# Power_module_Mini.net
KiCad netlist of a schematic drawn in EAGLE
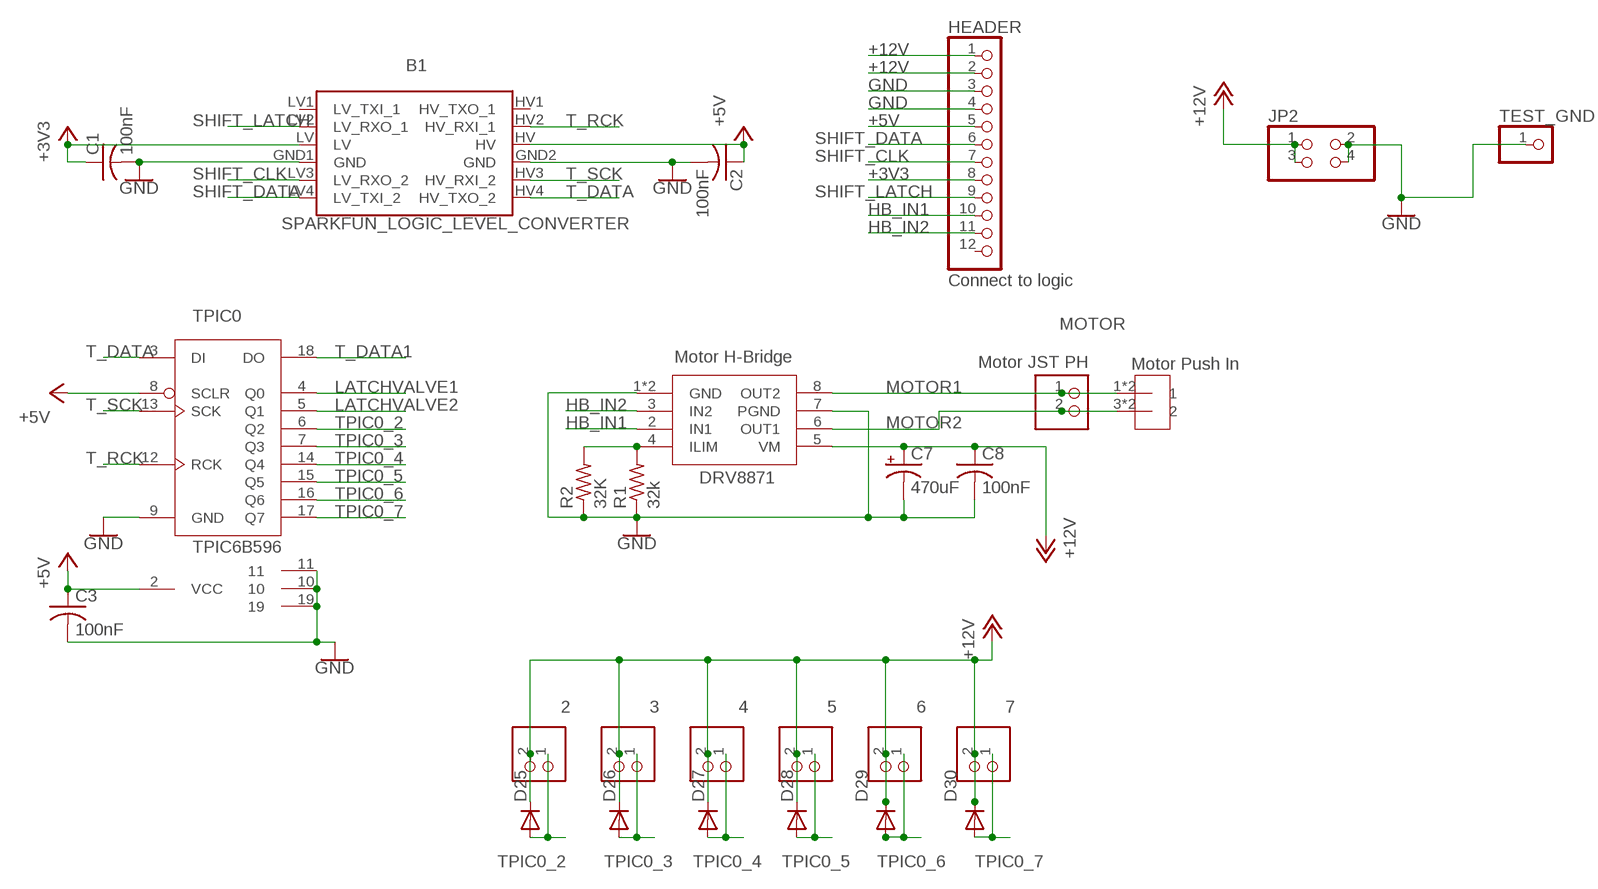
[diagram p0: schematic, sheet 1]

(export (version "E")
  (design (tool "Eeschema 10.0.6"))
  (components
    (comp (ref "2")
      (value "2.5MM_JST_UP_2POS")
      (footprint "eagle-import:JST_2POS_2.5MM_UP")
      (libsource (lib "eagle-import") (part "2.5MM_JST_UP_2POS"))
    )
    (comp (ref "3")
      (value "2.5MM_JST_UP_2POS")
      (footprint "eagle-import:JST_2POS_2.5MM_UP")
      (libsource (lib "eagle-import") (part "2.5MM_JST_UP_2POS"))
    )
    (comp (ref "4")
      (value "2.5MM_JST_UP_2POS")
      (footprint "eagle-import:JST_2POS_2.5MM_UP")
      (libsource (lib "eagle-import") (part "2.5MM_JST_UP_2POS"))
    )
    (comp (ref "5")
      (value "2.5MM_JST_UP_2POS")
      (footprint "eagle-import:JST_2POS_2.5MM_UP")
      (libsource (lib "eagle-import") (part "2.5MM_JST_UP_2POS"))
    )
    (comp (ref "6")
      (value "2.5MM_JST_UP_2POS")
      (footprint "eagle-import:JST_2POS_2.5MM_UP")
      (libsource (lib "eagle-import") (part "2.5MM_JST_UP_2POS"))
    )
    (comp (ref "7")
      (value "2.5MM_JST_UP_2POS")
      (footprint "eagle-import:JST_2POS_2.5MM_UP")
      (libsource (lib "eagle-import") (part "2.5MM_JST_UP_2POS"))
    )
    (comp (ref "B1")
      (value "SPARKFUN_LOGIC_LEVEL_CONVERTER")
      (footprint "eagle-import:SPARKFUN_LOGIC_LEVEL_CONVERTER")
      (libsource (lib "eagle-import") (part "SPARKFUN_LOGIC_LEVEL_CONVERTER"))
    )
    (comp (ref "C1")
      (value "100nF")
      (footprint "eagle-import:C1206")
      (libsource (lib "eagle-import") (part "C-USC1206"))
    )
    (comp (ref "C2")
      (value "100nF")
      (footprint "eagle-import:C1206")
      (libsource (lib "eagle-import") (part "C-USC1206"))
    )
    (comp (ref "C3")
      (value "100nF")
      (footprint "eagle-import:C1206")
      (libsource (lib "eagle-import") (part "C-USC1206"))
    )
    (comp (ref "C7")
      (value "470uF")
      (footprint "eagle-import:140CLH-0810")
      (libsource (lib "eagle-import") (part "CPOL-US140CLH-0810"))
    )
    (comp (ref "C8")
      (value "100nF")
      (footprint "eagle-import:C1206")
      (libsource (lib "eagle-import") (part "C-USC1206"))
    )
    (comp (ref "D25")
      (value "DIODESOD-123")
      (footprint "eagle-import:SOD-123")
      (libsource (lib "eagle-import") (part "DIODESOD-123"))
    )
    (comp (ref "D26")
      (value "DIODESOD-123")
      (footprint "eagle-import:SOD-123")
      (libsource (lib "eagle-import") (part "DIODESOD-123"))
    )
    (comp (ref "D27")
      (value "DIODESOD-123")
      (footprint "eagle-import:SOD-123")
      (libsource (lib "eagle-import") (part "DIODESOD-123"))
    )
    (comp (ref "D28")
      (value "DIODESOD-123")
      (footprint "eagle-import:SOD-123")
      (libsource (lib "eagle-import") (part "DIODESOD-123"))
    )
    (comp (ref "D29")
      (value "DIODESOD-123")
      (footprint "eagle-import:SOD-123")
      (libsource (lib "eagle-import") (part "DIODESOD-123"))
    )
    (comp (ref "D30")
      (value "DIODESOD-123")
      (footprint "eagle-import:SOD-123")
      (libsource (lib "eagle-import") (part "DIODESOD-123"))
    )
    (comp (ref "DRV8871")
      (value "Motor H-Bridge")
      (footprint "eagle-import:SOP8")
      (libsource (lib "eagle-import") (part "DRV8871"))
    )
    (comp (ref "HEADER")
      (value "Connect to logic")
      (footprint "eagle-import:1X12")
      (libsource (lib "eagle-import") (part "PINHD-1X12"))
    )
    (comp (ref "JP2")
      (value "PINHD-2X2")
      (footprint "eagle-import:2X02")
      (libsource (lib "eagle-import") (part "PINHD-2X2"))
    )
    (comp (ref "MOTOR")
      (value "Motor JST PH")
      (footprint "eagle-import:JST_2POS_2.5MM_UP")
      (libsource (lib "eagle-import") (part "2.5MM_JST_UP_2POS"))
    )
    (comp (ref "R1")
      (value "32k")
      (footprint "eagle-import:0204_5")
      (libsource (lib "eagle-import") (part "R-US_0204/5"))
    )
    (comp (ref "R2")
      (value "32K")
      (footprint "eagle-import:R0805")
      (libsource (lib "eagle-import") (part "rcl_334_R-US_R0805"))
    )
    (comp (ref "TEST_GND")
      (value "PINHD-1X1")
      (footprint "eagle-import:1X01")
      (libsource (lib "eagle-import") (part "PINHD-1X1"))
    )
    (comp (ref "TPIC0")
      (value "TPIC6B596")
      (footprint "eagle-import:DIP20")
      (libsource (lib "eagle-import") (part "TPIC6B596"))
    )
    (comp (ref "U$1")
      (value "Motor Push In")
      (footprint "eagle-import:3.5MM_DIP2")
      (libsource (lib "eagle-import") (part "PUSH_IN_2"))
    )
  )
  (nets
    (net (code "1") (name "+3V3") (class "Default")
      (node (ref "B1") (pin "LV") (pinfunction "LV_LV") (pintype "power_in"))
      (node (ref "C1") (pin "1") (pinfunction "1_1") (pintype "passive"))
      (node (ref "HEADER") (pin "8") (pinfunction "8_8") (pintype "passive"))
    )
    (net (code "2") (name "+5V") (class "Default")
      (node (ref "B1") (pin "HV") (pinfunction "HV_HV") (pintype "power_in"))
      (node (ref "C2") (pin "1") (pinfunction "1_1") (pintype "passive"))
      (node (ref "C3") (pin "1") (pinfunction "1_1") (pintype "passive"))
      (node (ref "HEADER") (pin "5") (pinfunction "5_5") (pintype "passive"))
      (node (ref "TPIC0") (pin "2") (pinfunction "VCC_2") (pintype "bidirectional"))
      (node (ref "TPIC0") (pin "8") (pinfunction "SCLR_8") (pintype "bidirectional"))
    )
    (net (code "3") (name "+12V") (class "Default")
      (node (ref "2") (pin "2") (pinfunction "2_2") (pintype "bidirectional"))
      (node (ref "3") (pin "2") (pinfunction "2_2") (pintype "bidirectional"))
      (node (ref "4") (pin "2") (pinfunction "2_2") (pintype "bidirectional"))
      (node (ref "5") (pin "2") (pinfunction "2_2") (pintype "bidirectional"))
      (node (ref "6") (pin "2") (pinfunction "2_2") (pintype "bidirectional"))
      (node (ref "7") (pin "2") (pinfunction "2_2") (pintype "bidirectional"))
      (node (ref "C7") (pin "+") (pinfunction "+_+") (pintype "passive"))
      (node (ref "C8") (pin "1") (pinfunction "1_1") (pintype "passive"))
      (node (ref "D25") (pin "C") (pinfunction "C_C") (pintype "passive"))
      (node (ref "D26") (pin "C") (pinfunction "C_C") (pintype "passive"))
      (node (ref "D27") (pin "C") (pinfunction "C_C") (pintype "passive"))
      (node (ref "D28") (pin "C") (pinfunction "C_C") (pintype "passive"))
      (node (ref "D29") (pin "C") (pinfunction "C_C") (pintype "passive"))
      (node (ref "D30") (pin "C") (pinfunction "C_C") (pintype "passive"))
      (node (ref "DRV8871") (pin "5") (pinfunction "VM_5") (pintype "bidirectional"))
      (node (ref "HEADER") (pin "1") (pinfunction "1_1") (pintype "passive"))
      (node (ref "HEADER") (pin "2") (pinfunction "2_2") (pintype "passive"))
      (node (ref "JP2") (pin "1") (pinfunction "1_1") (pintype "passive"))
      (node (ref "JP2") (pin "3") (pinfunction "3_3") (pintype "passive"))
    )
    (net (code "4") (name "/HB_IN1") (class "Default")
      (node (ref "DRV8871") (pin "2") (pinfunction "IN1_2") (pintype "bidirectional"))
      (node (ref "HEADER") (pin "10") (pinfunction "10_10") (pintype "passive"))
    )
    (net (code "5") (name "/HB_IN2") (class "Default")
      (node (ref "DRV8871") (pin "3") (pinfunction "IN2_3") (pintype "bidirectional"))
      (node (ref "HEADER") (pin "11") (pinfunction "11_11") (pintype "passive"))
    )
    (net (code "6") (name "/LATCHVALVE1") (class "Default")
      (node (ref "TPIC0") (pin "4") (pinfunction "Q0_4") (pintype "bidirectional"))
    )
    (net (code "7") (name "/LATCHVALVE2") (class "Default")
      (node (ref "TPIC0") (pin "5") (pinfunction "Q1_5") (pintype "bidirectional"))
    )
    (net (code "8") (name "/MOTOR1") (class "Default")
      (node (ref "DRV8871") (pin "8") (pinfunction "OUT2_8") (pintype "bidirectional"))
      (node (ref "MOTOR") (pin "1") (pinfunction "1_1") (pintype "bidirectional"))
      (node (ref "U$1") (pin "1") (pinfunction "1_1") (pintype "bidirectional"))
      (node (ref "U$1") (pin "2") (pinfunction "1_2") (pintype "bidirectional"))
    )
    (net (code "9") (name "/MOTOR2") (class "Default")
      (node (ref "DRV8871") (pin "6") (pinfunction "OUT1_6") (pintype "bidirectional"))
      (node (ref "MOTOR") (pin "2") (pinfunction "2_2") (pintype "bidirectional"))
      (node (ref "U$1") (pin "3") (pinfunction "2_3") (pintype "bidirectional"))
      (node (ref "U$1") (pin "4") (pinfunction "2_4") (pintype "bidirectional"))
    )
    (net (code "10") (name "/SHIFT_CLK") (class "Default")
      (node (ref "B1") (pin "LV3") (pinfunction "LV_RXO_2_LV3") (pintype "bidirectional"))
      (node (ref "HEADER") (pin "7") (pinfunction "7_7") (pintype "passive"))
    )
    (net (code "11") (name "/SHIFT_DATA") (class "Default")
      (node (ref "B1") (pin "LV4") (pinfunction "LV_TXI_2_LV4") (pintype "bidirectional"))
      (node (ref "HEADER") (pin "6") (pinfunction "6_6") (pintype "passive"))
    )
    (net (code "12") (name "/SHIFT_LATCH") (class "Default")
      (node (ref "B1") (pin "LV2") (pinfunction "LV_RXO_1_LV2") (pintype "bidirectional"))
      (node (ref "HEADER") (pin "9") (pinfunction "9_9") (pintype "passive"))
    )
    (net (code "13") (name "/TPIC0_2") (class "Default")
      (node (ref "2") (pin "1") (pinfunction "1_1") (pintype "bidirectional"))
      (node (ref "D25") (pin "A") (pinfunction "A_A") (pintype "passive"))
      (node (ref "TPIC0") (pin "6") (pinfunction "Q2_6") (pintype "bidirectional"))
    )
    (net (code "14") (name "/TPIC0_3") (class "Default")
      (node (ref "3") (pin "1") (pinfunction "1_1") (pintype "bidirectional"))
      (node (ref "D26") (pin "A") (pinfunction "A_A") (pintype "passive"))
      (node (ref "TPIC0") (pin "7") (pinfunction "Q3_7") (pintype "bidirectional"))
    )
    (net (code "15") (name "/TPIC0_4") (class "Default")
      (node (ref "4") (pin "1") (pinfunction "1_1") (pintype "bidirectional"))
      (node (ref "D27") (pin "A") (pinfunction "A_A") (pintype "passive"))
      (node (ref "TPIC0") (pin "14") (pinfunction "Q4_14") (pintype "bidirectional"))
    )
    (net (code "16") (name "/TPIC0_5") (class "Default")
      (node (ref "5") (pin "1") (pinfunction "1_1") (pintype "bidirectional"))
      (node (ref "D28") (pin "A") (pinfunction "A_A") (pintype "passive"))
      (node (ref "TPIC0") (pin "15") (pinfunction "Q5_15") (pintype "bidirectional"))
    )
    (net (code "17") (name "/TPIC0_6") (class "Default")
      (node (ref "6") (pin "1") (pinfunction "1_1") (pintype "bidirectional"))
      (node (ref "D29") (pin "A") (pinfunction "A_A") (pintype "passive"))
      (node (ref "TPIC0") (pin "16") (pinfunction "Q6_16") (pintype "bidirectional"))
    )
    (net (code "18") (name "/TPIC0_7") (class "Default")
      (node (ref "7") (pin "1") (pinfunction "1_1") (pintype "bidirectional"))
      (node (ref "D30") (pin "A") (pinfunction "A_A") (pintype "passive"))
      (node (ref "TPIC0") (pin "17") (pinfunction "Q7_17") (pintype "bidirectional"))
    )
    (net (code "19") (name "/T_DATA") (class "Default")
      (node (ref "B1") (pin "HV4") (pinfunction "HV_TXO_2_HV4") (pintype "bidirectional"))
      (node (ref "TPIC0") (pin "3") (pinfunction "DI_3") (pintype "bidirectional"))
    )
    (net (code "20") (name "/T_DATA1") (class "Default")
      (node (ref "TPIC0") (pin "18") (pinfunction "DO_18") (pintype "bidirectional"))
    )
    (net (code "21") (name "/T_RCK") (class "Default")
      (node (ref "B1") (pin "HV2") (pinfunction "HV_RXI_1_HV2") (pintype "bidirectional"))
      (node (ref "TPIC0") (pin "12") (pinfunction "RCK_12") (pintype "bidirectional"))
    )
    (net (code "22") (name "/T_SCK") (class "Default")
      (node (ref "B1") (pin "HV3") (pinfunction "HV_RXI_2_HV3") (pintype "bidirectional"))
      (node (ref "TPIC0") (pin "13") (pinfunction "SCK_13") (pintype "bidirectional"))
    )
    (net (code "23") (name "GND") (class "Default")
      (node (ref "B1") (pin "GND1") (pinfunction "GND_GND1") (pintype "power_in"))
      (node (ref "B1") (pin "GND2") (pinfunction "GND_GND2") (pintype "power_in"))
      (node (ref "C1") (pin "2") (pinfunction "2_2") (pintype "passive"))
      (node (ref "C2") (pin "2") (pinfunction "2_2") (pintype "passive"))
      (node (ref "C3") (pin "2") (pinfunction "2_2") (pintype "passive"))
      (node (ref "C7") (pin "-") (pinfunction "-_-") (pintype "passive"))
      (node (ref "C8") (pin "2") (pinfunction "2_2") (pintype "passive"))
      (node (ref "DRV8871") (pin "1") (pinfunction "GND_1") (pintype "bidirectional"))
      (node (ref "DRV8871") (pin "7") (pinfunction "PGND_7") (pintype "bidirectional"))
      (node (ref "DRV8871") (pin "GND") (pinfunction "GND_GND") (pintype "bidirectional"))
      (node (ref "HEADER") (pin "3") (pinfunction "3_3") (pintype "passive"))
      (node (ref "HEADER") (pin "4") (pinfunction "4_4") (pintype "passive"))
      (node (ref "JP2") (pin "2") (pinfunction "2_2") (pintype "passive"))
      (node (ref "JP2") (pin "4") (pinfunction "4_4") (pintype "passive"))
      (node (ref "R1") (pin "1") (pinfunction "1_1") (pintype "passive"))
      (node (ref "R2") (pin "1") (pinfunction "1_1") (pintype "passive"))
      (node (ref "TEST_GND") (pin "1") (pinfunction "1_1") (pintype "passive"))
      (node (ref "TPIC0") (pin "10") (pinfunction "10_10") (pintype "bidirectional"))
      (node (ref "TPIC0") (pin "11") (pinfunction "11_11") (pintype "bidirectional"))
      (node (ref "TPIC0") (pin "19") (pinfunction "19_19") (pintype "bidirectional"))
      (node (ref "TPIC0") (pin "9") (pinfunction "GND_9") (pintype "bidirectional"))
    )
    (net (code "24") (name "Net-(DRV8871-ILIM)") (class "Default")
      (node (ref "DRV8871") (pin "4") (pinfunction "ILIM_4") (pintype "bidirectional"))
      (node (ref "R1") (pin "2") (pinfunction "2_2") (pintype "passive"))
      (node (ref "R2") (pin "2") (pinfunction "2_2") (pintype "passive"))
    )
    (net (code "25") (name "unconnected-(B1-HV_TXO_1-PadHV1)") (class "Default")
      (node (ref "B1") (pin "HV1") (pinfunction "HV_TXO_1_HV1") (pintype "bidirectional"))
    )
    (net (code "26") (name "unconnected-(B1-LV_TXI_1-PadLV1)") (class "Default")
      (node (ref "B1") (pin "LV1") (pinfunction "LV_TXI_1_LV1") (pintype "bidirectional"))
    )
    (net (code "27") (name "unconnected-(HEADER-Pad12)") (class "Default")
      (node (ref "HEADER") (pin "12") (pinfunction "12_12") (pintype "passive"))
    )
  )
)
